# source_eagle.net
KiCad netlist of a schematic drawn in EAGLE
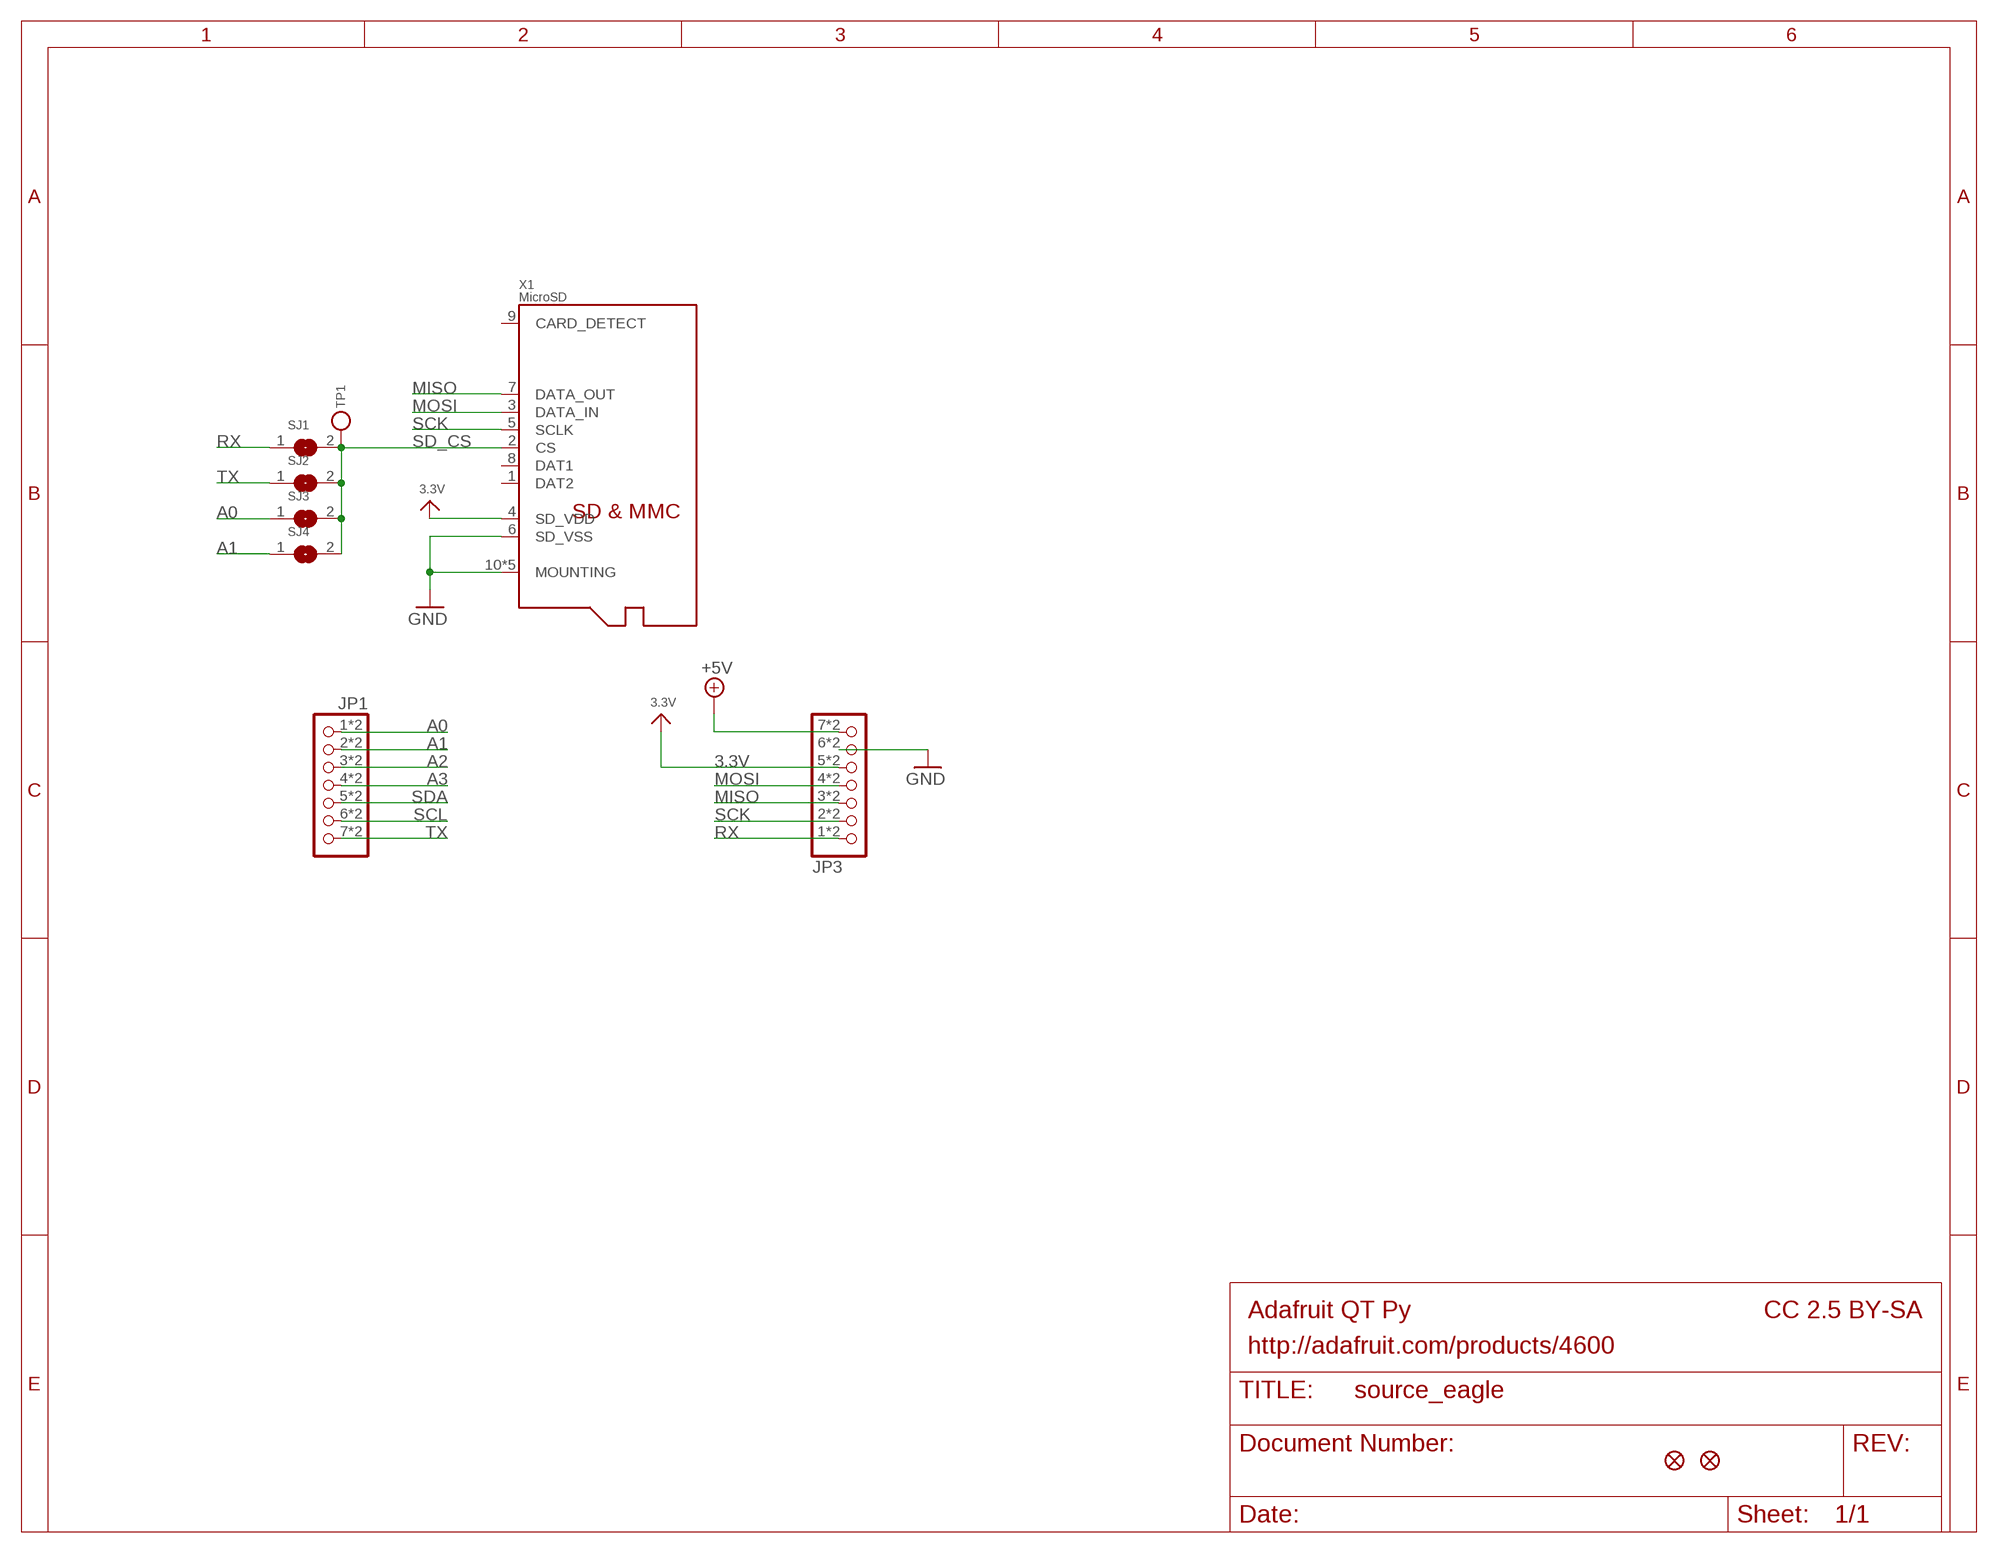
[diagram p0: schematic, sheet 1]

(export (version "E")
  (design (tool "Eeschema 10.0.6"))
  (components
    (comp (ref "JP1")
      (value "HEADER-1X7_CASTEL")
      (footprint "eagle-import:1X07_CASTEL")
      (libsource (lib "eagle-import") (part "HEADER-1X7_CASTEL"))
    )
    (comp (ref "JP3")
      (value "HEADER-1X7_CASTEL")
      (footprint "eagle-import:1X07_CASTEL")
      (libsource (lib "eagle-import") (part "HEADER-1X7_CASTEL"))
    )
    (comp (ref "SJ1")
      (value "SOLDERJUMPER")
      (footprint "eagle-import:SOLDERJUMPER_ARROW_NOPASTE")
      (libsource (lib "eagle-import") (part "SOLDERJUMPER"))
    )
    (comp (ref "SJ2")
      (value "SOLDERJUMPERCLOSED")
      (footprint "eagle-import:SOLDERJUMPER_CLOSEDWIRE")
      (libsource (lib "eagle-import") (part "SOLDERJUMPERCLOSED"))
    )
    (comp (ref "SJ3")
      (value "SOLDERJUMPER")
      (footprint "eagle-import:SOLDERJUMPER_ARROW_NOPASTE")
      (libsource (lib "eagle-import") (part "SOLDERJUMPER"))
    )
    (comp (ref "SJ4")
      (value "SOLDERJUMPER")
      (footprint "eagle-import:SOLDERJUMPER_ARROW_NOPASTE")
      (libsource (lib "eagle-import") (part "SOLDERJUMPER"))
    )
    (comp (ref "TP1")
      (value "TESTPOINTPAD1MM")
      (footprint "eagle-import:TESTPOINT_PAD_1MM")
      (libsource (lib "eagle-import") (part "TESTPOINTPAD1MM"))
    )
    (comp (ref "U$6")
      (value "FIDUCIAL_1MM")
      (footprint "eagle-import:FIDUCIAL_1MM")
      (libsource (lib "eagle-import") (part "FIDUCIAL_1MM"))
    )
    (comp (ref "U$8")
      (value "FIDUCIAL_1MM")
      (footprint "eagle-import:FIDUCIAL_1MM")
      (libsource (lib "eagle-import") (part "FIDUCIAL_1MM"))
    )
    (comp (ref "X1")
      (value "MicroSD")
      (footprint "eagle-import:MOLEX_104031-0811")
      (libsource (lib "eagle-import") (part "MICROSD104031-0811"))
    )
  )
  (nets
    (net (code "1") (name "+5V") (class "Default")
      (node (ref "JP3") (pin "7") (pinfunction "7_7") (pintype "passive"))
      (node (ref "JP3") (pin "7C") (pinfunction "7_7C") (pintype "passive"))
    )
    (net (code "2") (name "/A0") (class "Default")
      (node (ref "JP1") (pin "1") (pinfunction "1_1") (pintype "passive"))
      (node (ref "JP1") (pin "1C") (pinfunction "1_1C") (pintype "passive"))
      (node (ref "SJ3") (pin "1") (pinfunction "1_1") (pintype "passive"))
    )
    (net (code "3") (name "/A1") (class "Default")
      (node (ref "JP1") (pin "2") (pinfunction "2_2") (pintype "passive"))
      (node (ref "JP1") (pin "2C") (pinfunction "2_2C") (pintype "passive"))
      (node (ref "SJ4") (pin "1") (pinfunction "1_1") (pintype "passive"))
    )
    (net (code "4") (name "/A2") (class "Default")
      (node (ref "JP1") (pin "3") (pinfunction "3_3") (pintype "passive"))
      (node (ref "JP1") (pin "3C") (pinfunction "3_3C") (pintype "passive"))
    )
    (net (code "5") (name "/A3") (class "Default")
      (node (ref "JP1") (pin "4") (pinfunction "4_4") (pintype "passive"))
      (node (ref "JP1") (pin "4C") (pinfunction "4_4C") (pintype "passive"))
    )
    (net (code "6") (name "/MISO") (class "Default")
      (node (ref "JP3") (pin "3") (pinfunction "3_3") (pintype "passive"))
      (node (ref "JP3") (pin "3C") (pinfunction "3_3C") (pintype "passive"))
      (node (ref "X1") (pin "7") (pinfunction "DATA_OUT_7") (pintype "output"))
    )
    (net (code "7") (name "/MOSI") (class "Default")
      (node (ref "JP3") (pin "4") (pinfunction "4_4") (pintype "passive"))
      (node (ref "JP3") (pin "4C") (pinfunction "4_4C") (pintype "passive"))
      (node (ref "X1") (pin "3") (pinfunction "DATA_IN_3") (pintype "input"))
    )
    (net (code "8") (name "/RX") (class "Default")
      (node (ref "JP3") (pin "1") (pinfunction "1_1") (pintype "passive"))
      (node (ref "JP3") (pin "1C") (pinfunction "1_1C") (pintype "passive"))
      (node (ref "SJ1") (pin "1") (pinfunction "1_1") (pintype "passive"))
    )
    (net (code "9") (name "/SCK") (class "Default")
      (node (ref "JP3") (pin "2") (pinfunction "2_2") (pintype "passive"))
      (node (ref "JP3") (pin "2C") (pinfunction "2_2C") (pintype "passive"))
      (node (ref "X1") (pin "5") (pinfunction "SCLK_5") (pintype "input"))
    )
    (net (code "10") (name "/SCL") (class "Default")
      (node (ref "JP1") (pin "6") (pinfunction "6_6") (pintype "passive"))
      (node (ref "JP1") (pin "6C") (pinfunction "6_6C") (pintype "passive"))
    )
    (net (code "11") (name "/SDA") (class "Default")
      (node (ref "JP1") (pin "5") (pinfunction "5_5") (pintype "passive"))
      (node (ref "JP1") (pin "5C") (pinfunction "5_5C") (pintype "passive"))
    )
    (net (code "12") (name "/SD_CS") (class "Default")
      (node (ref "SJ1") (pin "2") (pinfunction "2_2") (pintype "passive"))
      (node (ref "SJ2") (pin "2") (pinfunction "2_2") (pintype "passive"))
      (node (ref "SJ3") (pin "2") (pinfunction "2_2") (pintype "passive"))
      (node (ref "SJ4") (pin "2") (pinfunction "2_2") (pintype "passive"))
      (node (ref "TP1") (pin "P$1") (pinfunction "P$1_P$1") (pintype "bidirectional"))
      (node (ref "X1") (pin "2") (pinfunction "CS_2") (pintype "input"))
    )
    (net (code "13") (name "/TX") (class "Default")
      (node (ref "JP1") (pin "7") (pinfunction "7_7") (pintype "passive"))
      (node (ref "JP1") (pin "7C") (pinfunction "7_7C") (pintype "passive"))
      (node (ref "SJ2") (pin "1") (pinfunction "1_1") (pintype "passive"))
    )
    (net (code "14") (name "3.3V") (class "Default")
      (node (ref "JP3") (pin "5") (pinfunction "5_5") (pintype "passive"))
      (node (ref "JP3") (pin "5C") (pinfunction "5_5C") (pintype "passive"))
      (node (ref "X1") (pin "4") (pinfunction "SD_VDD_4") (pintype "power_in"))
    )
    (net (code "15") (name "GND") (class "Default")
      (node (ref "JP3") (pin "6") (pinfunction "6_6") (pintype "passive"))
      (node (ref "JP3") (pin "6C") (pinfunction "6_6C") (pintype "passive"))
      (node (ref "X1") (pin "10") (pinfunction "MOUNTING_10") (pintype "passive"))
      (node (ref "X1") (pin "6") (pinfunction "SD_VSS_6") (pintype "power_in"))
      (node (ref "X1") (pin "G1") (pinfunction "MOUNTING_G1") (pintype "passive"))
      (node (ref "X1") (pin "G2") (pinfunction "MOUNTING_G2") (pintype "passive"))
      (node (ref "X1") (pin "G3") (pinfunction "MOUNTING_G3") (pintype "passive"))
      (node (ref "X1") (pin "G4") (pinfunction "MOUNTING_G4") (pintype "passive"))
    )
    (net (code "16") (name "unconnected-(X1-CARD_DETECT-Pad9)") (class "Default")
      (node (ref "X1") (pin "9") (pinfunction "CARD_DETECT_9") (pintype "passive"))
    )
    (net (code "17") (name "unconnected-(X1-DAT1-Pad8)") (class "Default")
      (node (ref "X1") (pin "8") (pinfunction "DAT1_8") (pintype "bidirectional"))
    )
    (net (code "18") (name "unconnected-(X1-DAT2-Pad1)") (class "Default")
      (node (ref "X1") (pin "1") (pinfunction "DAT2_1") (pintype "bidirectional"))
    )
  )
)
